# PowerSupply.net
KiCad netlist of a schematic drawn in Altium Designer
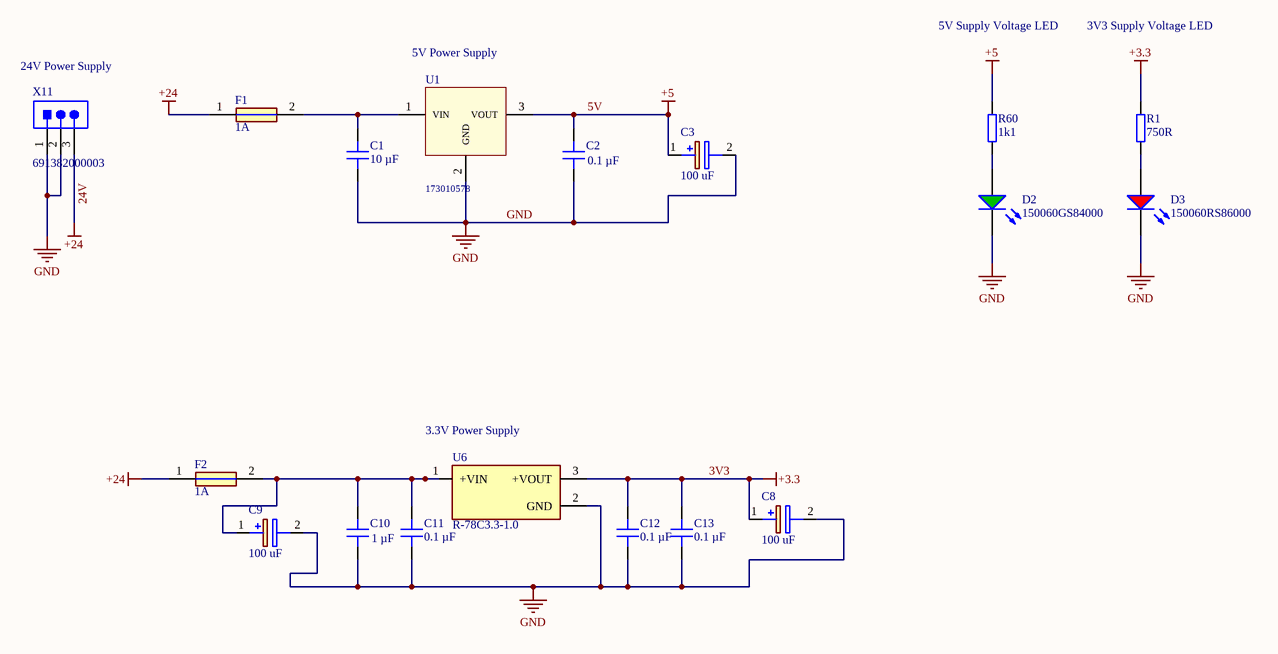
[diagram p0: PowerSupply.SchDoc]

(export (version "E")
  (design (tool "Eeschema 10.0.6"))
  (components
    (comp (ref "C1")
      (value "10 µF")
      (footprint "C_0805")
      (description "Capacitor 0805, 25 VDC, 10 µF, X5R")
      (fields
        (field (name "MANUFACTURER PART NUMBER") "GRM219R61E106KA12D")
        (field (name "MANUFACTURER") "muRata")
        (field (name "CREATED FROM") "MGremer")
      )
      (libsource (lib "user") (part "Capacitor"))
    )
    (comp (ref "C2")
      (value "0.1 µF")
      (footprint "C_0603")
      (description "Capacitor 0603, 25 VDC, 0.1 µF, X7R")
      (fields
        (field (name "MANUFACTURER PART NUMBER") "C0603C104J3REC7411")
        (field (name "MANUFACTURER") "KEMET")
        (field (name "CREATED FROM") "MGremer")
      )
      (libsource (lib "user") (part "Capacitor"))
    )
    (comp (ref "C3")
      (value "100 uF")
      (footprint "CAPAE660X610N")
      (description "Capacitor EEE, 6.3VDC, 100uF")
      (fields
        (field (name "MANUFACTURER PART NUMBER") "EEE-FK0J101V")
        (field (name "MANUFACTURER") "Panasonic")
        (field (name "CREATED FROM") "TWilfling")
      )
      (libsource (lib "user") (part "EEE-FK0J101V"))
    )
    (comp (ref "C8")
      (value "100 uF")
      (footprint "CAPAE1270X1400N")
      (description "Capacitor Al Electrolyt, 100 uF, 50VDC")
      (fields
        (field (name "MANUFACTURER PART NUMBER") "MAL216099101E3")
        (field (name "MANUFACTURER") "Vishay")
        (field (name "CREATED FROM") "TWilfling")
      )
      (libsource (lib "user") (part "MAL216099101E3"))
    )
    (comp (ref "C9")
      (value "100 uF")
      (footprint "CAPAE1270X1400N")
      (description "Capacitor Al Electrolyt, 100 uF, 50VDC")
      (fields
        (field (name "MANUFACTURER PART NUMBER") "MAL216099101E3")
        (field (name "MANUFACTURER") "Vishay")
        (field (name "CREATED FROM") "TWilfling")
      )
      (libsource (lib "user") (part "MAL216099101E3"))
    )
    (comp (ref "C10")
      (value "1 µF")
      (footprint "C_0603")
      (description "Capacitor 0603, 50 VDC, 1 µF, X7R")
      (fields
        (field (name "MANUFACTURER PART NUMBER") "UMK107AB7105KA-T")
        (field (name "MANUFACTURER") "Taiyo Yuden")
        (field (name "CREATED FROM") "MGremer")
      )
      (libsource (lib "user") (part "Capacitor"))
    )
    (comp (ref "C11")
      (value "0.1 µF")
      (footprint "C_0603")
      (description "Capacitor 0603, 50 VDC, 0.1 µF, X7R")
      (fields
        (field (name "MANUFACTURER PART NUMBER") "C0603X104K5RAC7411")
        (field (name "MANUFACTURER") "KEMET")
        (field (name "CREATED FROM") "MGremer")
      )
      (libsource (lib "user") (part "Capacitor"))
    )
    (comp (ref "C12")
      (value "0.1 µF")
      (footprint "C_0603")
      (description "Capacitor 0603, 50 VDC, 0.1 µF, X7R")
      (fields
        (field (name "MANUFACTURER PART NUMBER") "C0603X104K5RAC7411")
        (field (name "MANUFACTURER") "KEMET")
        (field (name "CREATED FROM") "MGremer")
      )
      (libsource (lib "user") (part "Capacitor"))
    )
    (comp (ref "C13")
      (value "0.1 µF")
      (footprint "C_0603")
      (description "Capacitor 0603, 50 VDC, 0.1 µF, X7R")
      (fields
        (field (name "MANUFACTURER PART NUMBER") "C0603X104K5RAC7411")
        (field (name "MANUFACTURER") "KEMET")
        (field (name "CREATED FROM") "MGremer")
      )
      (libsource (lib "user") (part "Capacitor"))
    )
    (comp (ref "D2")
      (value "150060GS84000")
      (footprint "WL-SMCW_0603")
      (description "WL-SMCW SMD Mono-color Chip LED Waterclear Green")
      (fields (field (name "MANUFACTURER") "Wuerth Elektronik") (field (name "CREATED FROM") "MGremer"))
      (libsource (lib "user") (part "LED_Green"))
    )
    (comp (ref "D3")
      (value "150060RS86000")
      (footprint "WL-SMCW_0603")
      (description "WL-SMCW SMD Mono-color Chip LED Waterclear Red")
      (fields (field (name "MANUFACTURER") "Wuerth Elektronik") (field (name "CREATED FROM") "MGremer"))
      (libsource (lib "user") (part "LED_Red"))
    )
    (comp (ref "F1")
      (value "1A")
      (footprint "Littlefuse_154")
      (description "Duse OMNI BLOK 154")
      (fields
        (field (name "MANUFACTURER PART NUMBER") "0154001.DR")
        (field (name "MANUFACTURER") "Littelfuse")
        (field (name "CREATED FROM") "TWilfling")
      )
      (libsource (lib "user") (part "0154001.DR"))
    )
    (comp (ref "F2")
      (value "1A")
      (footprint "Littlefuse_154")
      (description "Duse OMNI BLOK 154")
      (fields
        (field (name "MANUFACTURER PART NUMBER") "0154001.DR")
        (field (name "MANUFACTURER") "Littelfuse")
        (field (name "CREATED FROM") "TWilfling")
      )
      (libsource (lib "user") (part "0154001.DR"))
    )
    (comp (ref "R1")
      (value "750R")
      (footprint "RES 0603_1608")
      (description "SMD resistor E24 series")
      (fields
        (field (name "MANUFACTURER PART NUMBER") "RK73B1JTTDD751J")
        (field (name "MANUFACTURER") "KOA Speer")
        (field (name "CREATED FROM") "MGremer")
      )
      (libsource (lib "user") (part "Resistor"))
    )
    (comp (ref "R60")
      (value "1k1")
      (footprint "RES 0603_1608")
      (description "SMD resistor E24 series")
      (fields
        (field (name "MANUFACTURER PART NUMBER") "RK73B1JTTDD112J")
        (field (name "MANUFACTURER") "KOA Speer")
        (field (name "CREATED FROM") "MGremer")
      )
      (libsource (lib "user") (part "Resistor"))
    )
    (comp (ref "U1")
      (value "173010578")
      (footprint "FDSM_SIP-3")
      (description "Not isolated DCDC Converter 5 V Output, 1 A, 8 - 28 V Input")
      (fields (field (name "MANUFACTURER") "Wuerth Elektronik") (field (name "CREATED FROM") "MGremer"))
      (libsource (lib "user") (part "173010578"))
    )
    (comp (ref "U6")
      (value "R-78C3.3-1.0")
      (footprint "CONV_R-78C3.3-1.0")
      (description "Not isolated DCDC Converter 3V3 Output, 1A, 7 - 42V Input")
      (fields (field (name "MANUFACTURER") "RECOM") (field (name "CREATED FROM") "TWilfling"))
      (libsource (lib "user") (part "R-78C3.3-1.0"))
    )
    (comp (ref "X11")
      (value "691382000003")
      (footprint "691382000003")
      (description "2.5mm Single Row 3-pol Vertical PCB Header")
      (fields (field (name "MANUFACTURER") "Wurth") (field (name "CREATED FROM") "TWilfling"))
      (libsource (lib "user") (part "691382000003"))
    )
  )
  (nets
    (net (code "1") (name "+3.3") (class "Default")
      (node (ref "C12") (pin "2") (pinfunction "2_2") (pintype "passive"))
      (node (ref "C13") (pin "2") (pinfunction "2_2") (pintype "passive"))
      (node (ref "C8") (pin "1") (pinfunction "+_1") (pintype "passive"))
      (node (ref "R1") (pin "2") (pinfunction "2_2") (pintype "passive"))
      (node (ref "U6") (pin "3") (pinfunction "+VOUT_3") (pintype "passive"))
    )
    (net (code "2") (name "+5") (class "Default")
      (node (ref "C2") (pin "2") (pinfunction "2_2") (pintype "passive"))
      (node (ref "C3") (pin "1") (pinfunction "+_1") (pintype "passive"))
      (node (ref "R60") (pin "2") (pinfunction "2_2") (pintype "passive"))
      (node (ref "U1") (pin "3") (pinfunction "VOUT_3") (pintype "passive"))
    )
    (net (code "3") (name "+24") (class "Default")
      (node (ref "F1") (pin "1") (pinfunction "1_1") (pintype "passive"))
      (node (ref "F2") (pin "1") (pinfunction "1_1") (pintype "passive"))
      (node (ref "X11") (pin "3") (pinfunction "3_3") (pintype "passive"))
    )
    (net (code "4") (name "GND") (class "Default")
      (node (ref "C1") (pin "1") (pinfunction "1_1") (pintype "passive"))
      (node (ref "C10") (pin "1") (pinfunction "1_1") (pintype "passive"))
      (node (ref "C11") (pin "1") (pinfunction "1_1") (pintype "passive"))
      (node (ref "C12") (pin "1") (pinfunction "1_1") (pintype "passive"))
      (node (ref "C13") (pin "1") (pinfunction "1_1") (pintype "passive"))
      (node (ref "C2") (pin "1") (pinfunction "1_1") (pintype "passive"))
      (node (ref "C3") (pin "2") (pinfunction "-_2") (pintype "passive"))
      (node (ref "C8") (pin "2") (pinfunction "-_2") (pintype "passive"))
      (node (ref "C9") (pin "2") (pinfunction "-_2") (pintype "passive"))
      (node (ref "D2") (pin "1") (pinfunction "K_1") (pintype "passive"))
      (node (ref "D3") (pin "1") (pinfunction "K_1") (pintype "passive"))
      (node (ref "U1") (pin "2") (pinfunction "GND_2") (pintype "passive"))
      (node (ref "U6") (pin "2") (pinfunction "GND_2") (pintype "passive"))
      (node (ref "X11") (pin "1") (pinfunction "1_1") (pintype "passive"))
      (node (ref "X11") (pin "2") (pinfunction "2_2") (pintype "passive"))
    )
    (net (code "5") (name "Net-(C9-+)") (class "Default")
      (node (ref "C10") (pin "2") (pinfunction "2_2") (pintype "passive"))
      (node (ref "C11") (pin "2") (pinfunction "2_2") (pintype "passive"))
      (node (ref "C9") (pin "1") (pinfunction "+_1") (pintype "passive"))
      (node (ref "F2") (pin "2") (pinfunction "2_2") (pintype "passive"))
      (node (ref "U6") (pin "1") (pinfunction "+VIN_1") (pintype "passive"))
    )
    (net (code "6") (name "Net-(D2-A)") (class "Default")
      (node (ref "D2") (pin "2") (pinfunction "A_2") (pintype "passive"))
      (node (ref "R60") (pin "1") (pinfunction "1_1") (pintype "passive"))
    )
    (net (code "7") (name "Net-(D3-A)") (class "Default")
      (node (ref "D3") (pin "2") (pinfunction "A_2") (pintype "passive"))
      (node (ref "R1") (pin "1") (pinfunction "1_1") (pintype "passive"))
    )
    (net (code "8") (name "Net-(U1-VIN)") (class "Default")
      (node (ref "C1") (pin "2") (pinfunction "2_2") (pintype "passive"))
      (node (ref "F1") (pin "2") (pinfunction "2_2") (pintype "passive"))
      (node (ref "U1") (pin "1") (pinfunction "VIN_1") (pintype "passive"))
    )
  )
)
